# carte_Moteurs.net
KiCad netlist of a schematic drawn in EAGLE
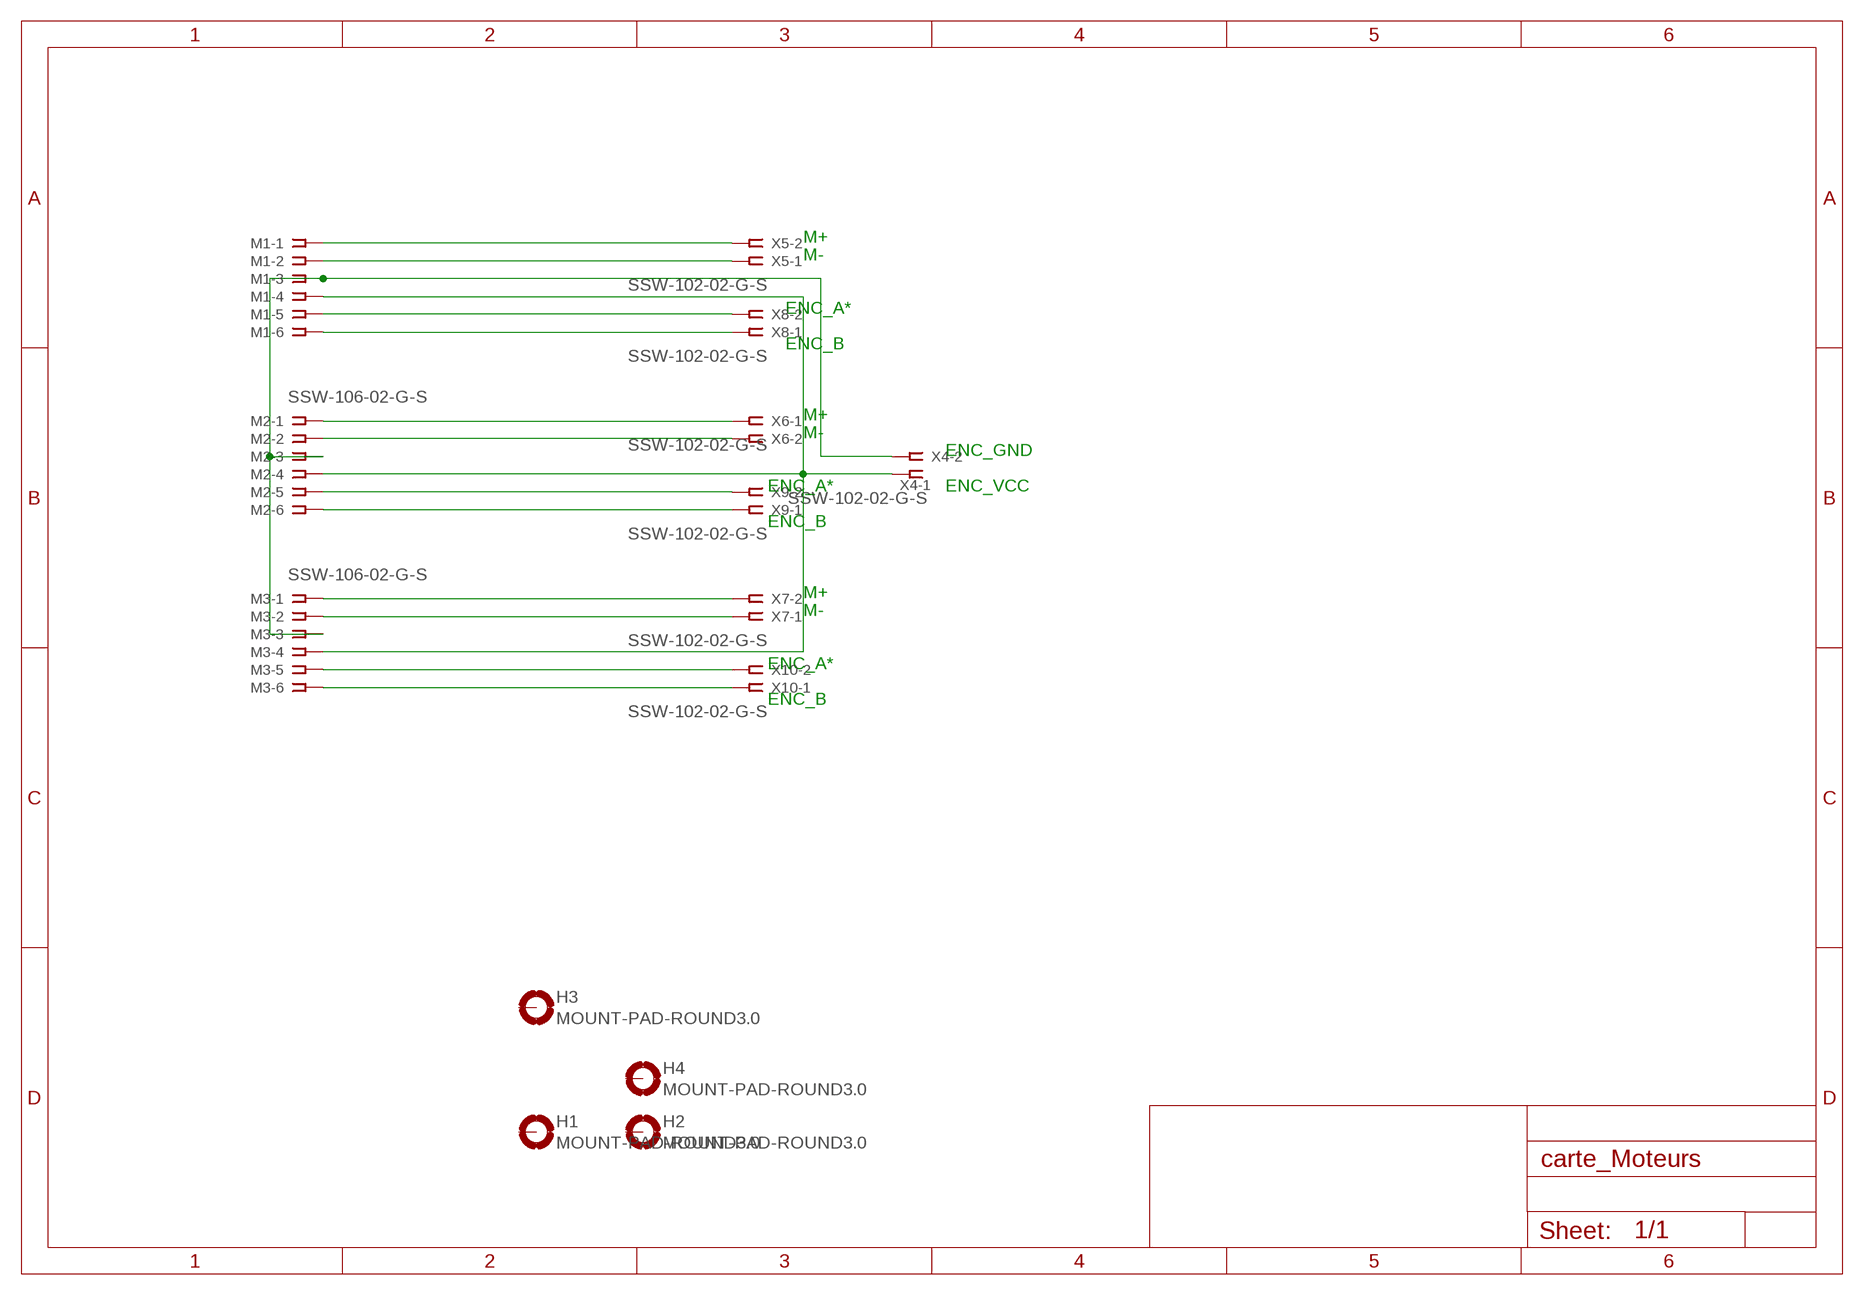
[diagram p0: schematic, sheet 1]

(export (version "E")
  (design (tool "Eeschema 10.0.6"))
  (components
    (comp (ref "H1")
      (value "MOUNT-PAD-ROUND3.0")
      (footprint "eagle-import:3,0-PAD")
      (libsource (lib "eagle-import") (part "MOUNT-PAD-ROUND3.0"))
    )
    (comp (ref "H2")
      (value "MOUNT-PAD-ROUND3.0")
      (footprint "eagle-import:3,0-PAD")
      (libsource (lib "eagle-import") (part "MOUNT-PAD-ROUND3.0"))
    )
    (comp (ref "H3")
      (value "MOUNT-PAD-ROUND3.0")
      (footprint "eagle-import:3,0-PAD")
      (libsource (lib "eagle-import") (part "MOUNT-PAD-ROUND3.0"))
    )
    (comp (ref "H4")
      (value "MOUNT-PAD-ROUND3.0")
      (footprint "eagle-import:3,0-PAD")
      (libsource (lib "eagle-import") (part "MOUNT-PAD-ROUND3.0"))
    )
    (comp (ref "M1")
      (value "SSW-106-02-G-S")
      (footprint "eagle-import:SSW-106-02-G-S")
      (fields (field (name "MF") "Samtec Inc.") (field (name "MPN") "Motor1"))
      (libsource (lib "eagle-import") (part "SSW-106-02-G-S"))
    )
    (comp (ref "M2")
      (value "SSW-106-02-G-S")
      (footprint "eagle-import:SSW-106-02-G-S")
      (fields (field (name "MF") "Samtec Inc."))
      (libsource (lib "eagle-import") (part "SSW-106-02-G-S"))
    )
    (comp (ref "M3")
      (value "SSW-106-02-G-S")
      (footprint "eagle-import:SSW-106-02-G-S")
      (fields (field (name "MF") "Samtec Inc."))
      (libsource (lib "eagle-import") (part "SSW-106-02-G-S"))
    )
    (comp (ref "X4")
      (value "SSW-102-02-G-S")
      (footprint "eagle-import:SSW-102-02-G-S")
      (fields (field (name "MF") "Samtec Inc."))
      (libsource (lib "eagle-import") (part "SSW-102-02-G-S"))
    )
    (comp (ref "X5")
      (value "SSW-102-02-G-S")
      (footprint "eagle-import:SSW-102-02-G-S")
      (fields (field (name "MF") "Samtec Inc."))
      (libsource (lib "eagle-import") (part "SSW-102-02-G-S"))
    )
    (comp (ref "X6")
      (value "SSW-102-02-G-S")
      (footprint "eagle-import:SSW-102-02-G-S")
      (fields (field (name "MF") "Samtec Inc."))
      (libsource (lib "eagle-import") (part "SSW-102-02-G-S"))
    )
    (comp (ref "X7")
      (value "SSW-102-02-G-S")
      (footprint "eagle-import:SSW-102-02-G-S")
      (fields (field (name "MF") "Samtec Inc."))
      (libsource (lib "eagle-import") (part "SSW-102-02-G-S"))
    )
    (comp (ref "X8")
      (value "SSW-102-02-G-S")
      (footprint "eagle-import:SSW-102-02-G-S")
      (fields (field (name "MF") "Samtec Inc."))
      (libsource (lib "eagle-import") (part "SSW-102-02-G-S"))
    )
    (comp (ref "X9")
      (value "SSW-102-02-G-S")
      (footprint "eagle-import:SSW-102-02-G-S")
      (fields (field (name "MF") "Samtec Inc."))
      (libsource (lib "eagle-import") (part "SSW-102-02-G-S"))
    )
    (comp (ref "X10")
      (value "SSW-102-02-G-S")
      (footprint "eagle-import:SSW-102-02-G-S")
      (fields (field (name "MF") "Samtec Inc."))
      (libsource (lib "eagle-import") (part "SSW-102-02-G-S"))
    )
  )
  (nets
    (net (code "1") (name "Net-(M1B-1)") (class "Default")
      (node (ref "M1") (pin "2") (pinfunction "1_2") (pintype "passive"))
      (node (ref "X5") (pin "1") (pinfunction "1_1") (pintype "passive"))
    )
    (net (code "2") (name "Net-(M1C-1)") (class "Default")
      (node (ref "M1") (pin "3") (pinfunction "1_3") (pintype "passive"))
      (node (ref "M2") (pin "3") (pinfunction "1_3") (pintype "passive"))
      (node (ref "M3") (pin "3") (pinfunction "1_3") (pintype "passive"))
      (node (ref "X4") (pin "2") (pinfunction "1_2") (pintype "passive"))
    )
    (net (code "3") (name "Net-(M1D-1)") (class "Default")
      (node (ref "M1") (pin "4") (pinfunction "1_4") (pintype "passive"))
      (node (ref "M2") (pin "4") (pinfunction "1_4") (pintype "passive"))
      (node (ref "M3") (pin "4") (pinfunction "1_4") (pintype "passive"))
      (node (ref "X4") (pin "1") (pinfunction "1_1") (pintype "passive"))
    )
    (net (code "4") (name "Net-(M1E-1)") (class "Default")
      (node (ref "M1") (pin "5") (pinfunction "1_5") (pintype "passive"))
      (node (ref "X8") (pin "2") (pinfunction "1_2") (pintype "passive"))
    )
    (net (code "5") (name "Net-(M1F-1)") (class "Default")
      (node (ref "M1") (pin "6") (pinfunction "1_6") (pintype "passive"))
      (node (ref "X8") (pin "1") (pinfunction "1_1") (pintype "passive"))
    )
    (net (code "6") (name "Net-(M2-Pad1)") (class "Default")
      (node (ref "M2") (pin "1") (pinfunction "1_1") (pintype "passive"))
      (node (ref "X6") (pin "1") (pinfunction "1_1") (pintype "passive"))
    )
    (net (code "7") (name "Net-(M2B-1)") (class "Default")
      (node (ref "M2") (pin "2") (pinfunction "1_2") (pintype "passive"))
      (node (ref "X6") (pin "2") (pinfunction "1_2") (pintype "passive"))
    )
    (net (code "8") (name "Net-(M2E-1)") (class "Default")
      (node (ref "M2") (pin "5") (pinfunction "1_5") (pintype "passive"))
      (node (ref "X9") (pin "2") (pinfunction "1_2") (pintype "passive"))
    )
    (net (code "9") (name "Net-(M2F-1)") (class "Default")
      (node (ref "M2") (pin "6") (pinfunction "1_6") (pintype "passive"))
      (node (ref "X9") (pin "1") (pinfunction "1_1") (pintype "passive"))
    )
    (net (code "10") (name "Net-(M3B-1)") (class "Default")
      (node (ref "M3") (pin "2") (pinfunction "1_2") (pintype "passive"))
      (node (ref "X7") (pin "1") (pinfunction "1_1") (pintype "passive"))
    )
    (net (code "11") (name "Net-(M3E-1)") (class "Default")
      (node (ref "M3") (pin "5") (pinfunction "1_5") (pintype "passive"))
      (node (ref "X10") (pin "2") (pinfunction "1_2") (pintype "passive"))
    )
    (net (code "12") (name "Net-(M3F-1)") (class "Default")
      (node (ref "M3") (pin "6") (pinfunction "1_6") (pintype "passive"))
      (node (ref "X10") (pin "1") (pinfunction "1_1") (pintype "passive"))
    )
    (net (code "13") (name "Net-(X5B-1)") (class "Default")
      (node (ref "M1") (pin "1") (pinfunction "1_1") (pintype "passive"))
      (node (ref "X5") (pin "2") (pinfunction "1_2") (pintype "passive"))
    )
    (net (code "14") (name "Net-(X7B-1)") (class "Default")
      (node (ref "M3") (pin "1") (pinfunction "1_1") (pintype "passive"))
      (node (ref "X7") (pin "2") (pinfunction "1_2") (pintype "passive"))
    )
    (net (code "15") (name "unconnected-(H1-MOUNT-PadB3,0)") (class "Default")
      (node (ref "H1") (pin "B3,0") (pinfunction "MOUNT_B3,0") (pintype "passive"))
    )
    (net (code "16") (name "unconnected-(H2-MOUNT-PadB3,0)") (class "Default")
      (node (ref "H2") (pin "B3,0") (pinfunction "MOUNT_B3,0") (pintype "passive"))
    )
    (net (code "17") (name "unconnected-(H3-MOUNT-PadB3,0)") (class "Default")
      (node (ref "H3") (pin "B3,0") (pinfunction "MOUNT_B3,0") (pintype "passive"))
    )
    (net (code "18") (name "unconnected-(H4-MOUNT-PadB3,0)") (class "Default")
      (node (ref "H4") (pin "B3,0") (pinfunction "MOUNT_B3,0") (pintype "passive"))
    )
  )
)
